# BTB_CONNECTOR.net
KiCad netlist of a schematic drawn in Altium Designer
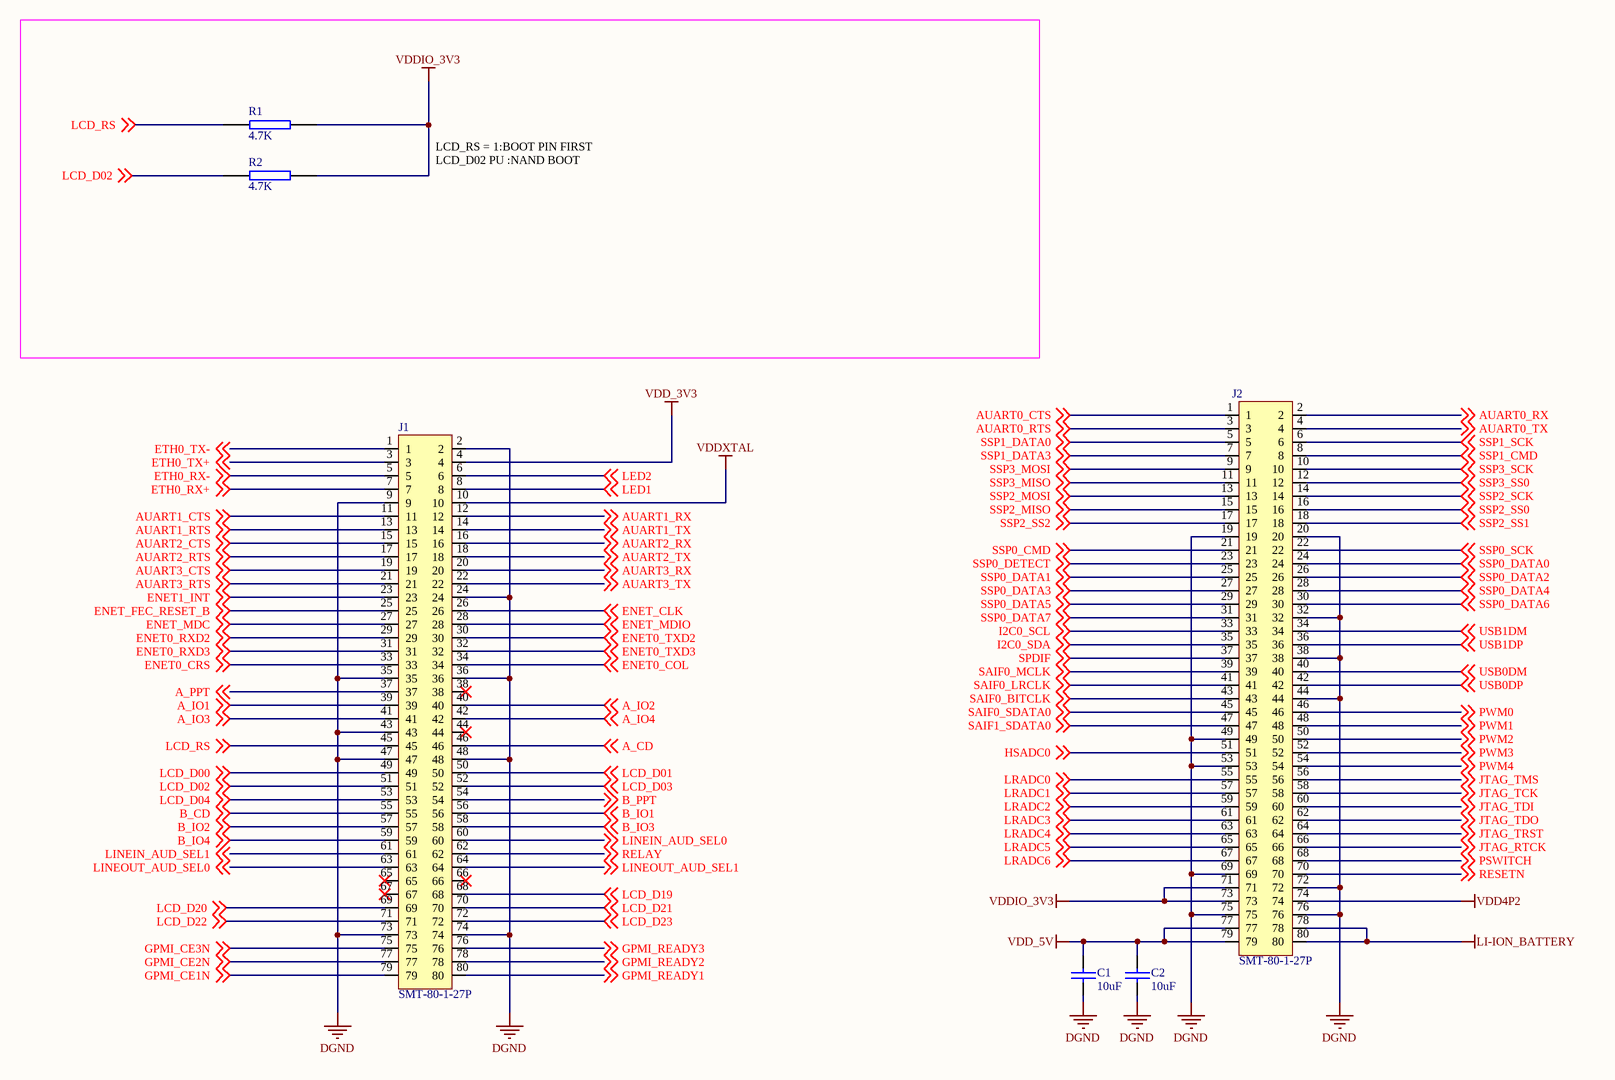
[diagram p0: BTB CONNECTOR.SchDoc]

(export (version "E")
  (design (tool "Eeschema 10.0.6"))
  (components
    (comp (ref "C1")
      (value "10uF")
      (footprint "C0805")
      (description "Capacitor")
      (libsource (lib "AirGateway") (part "CAP"))
    )
    (comp (ref "C2")
      (value "10uF")
      (footprint "C0805")
      (description "Capacitor")
      (libsource (lib "AirGateway") (part "CAP"))
    )
    (comp (ref "J1")
      (value "SMT-80-1-27P")
      (footprint "DB40X2-1.27")
      (libsource (lib "Schlib1") (part "SMT-80-1-27P"))
    )
    (comp (ref "J2")
      (value "SMT-80-1-27P")
      (footprint "DB40X2-1.27")
      (libsource (lib "Schlib1") (part "SMT-80-1-27P"))
    )
    (comp (ref "R1") (value "4.7K") (footprint "0603") (libsource (lib "AirGateway") (part "RES2")))
    (comp (ref "R2") (value "4.7K") (footprint "0603") (libsource (lib "AirGateway") (part "RES2")))
  )
  (nets
    (net (code "1") (name "AUART0_CTS") (class "Default")
      (node (ref "J2") (pin "1") (pinfunction "1_1") (pintype "passive"))
    )
    (net (code "2") (name "AUART0_RTS") (class "Default")
      (node (ref "J2") (pin "3") (pinfunction "3_3") (pintype "passive"))
    )
    (net (code "3") (name "AUART0_RX") (class "Default")
      (node (ref "J2") (pin "2") (pinfunction "2_2") (pintype "passive"))
    )
    (net (code "4") (name "AUART0_TX") (class "Default")
      (node (ref "J2") (pin "4") (pinfunction "4_4") (pintype "passive"))
    )
    (net (code "5") (name "AUART1_CTS") (class "Default")
      (node (ref "J1") (pin "11") (pinfunction "11_11") (pintype "passive"))
    )
    (net (code "6") (name "AUART1_RTS") (class "Default")
      (node (ref "J1") (pin "13") (pinfunction "13_13") (pintype "passive"))
    )
    (net (code "7") (name "AUART1_RX") (class "Default")
      (node (ref "J1") (pin "12") (pinfunction "12_12") (pintype "passive"))
    )
    (net (code "8") (name "AUART1_TX") (class "Default")
      (node (ref "J1") (pin "14") (pinfunction "14_14") (pintype "passive"))
    )
    (net (code "9") (name "AUART2_CTS") (class "Default")
      (node (ref "J1") (pin "15") (pinfunction "15_15") (pintype "passive"))
    )
    (net (code "10") (name "AUART2_RTS") (class "Default")
      (node (ref "J1") (pin "17") (pinfunction "17_17") (pintype "passive"))
    )
    (net (code "11") (name "AUART2_RX") (class "Default")
      (node (ref "J1") (pin "16") (pinfunction "16_16") (pintype "passive"))
    )
    (net (code "12") (name "AUART2_TX") (class "Default")
      (node (ref "J1") (pin "18") (pinfunction "18_18") (pintype "passive"))
    )
    (net (code "13") (name "AUART3_CTS") (class "Default")
      (node (ref "J1") (pin "19") (pinfunction "19_19") (pintype "passive"))
    )
    (net (code "14") (name "AUART3_RTS") (class "Default")
      (node (ref "J1") (pin "21") (pinfunction "21_21") (pintype "passive"))
    )
    (net (code "15") (name "AUART3_RX") (class "Default")
      (node (ref "J1") (pin "20") (pinfunction "20_20") (pintype "passive"))
    )
    (net (code "16") (name "AUART3_TX") (class "Default")
      (node (ref "J1") (pin "22") (pinfunction "22_22") (pintype "passive"))
    )
    (net (code "17") (name "A_CD") (class "Default")
      (node (ref "J1") (pin "46") (pinfunction "46_46") (pintype "passive"))
    )
    (net (code "18") (name "A_IO1") (class "Default")
      (node (ref "J1") (pin "39") (pinfunction "39_39") (pintype "passive"))
    )
    (net (code "19") (name "A_IO2") (class "Default")
      (node (ref "J1") (pin "40") (pinfunction "40_40") (pintype "passive"))
    )
    (net (code "20") (name "A_IO3") (class "Default")
      (node (ref "J1") (pin "41") (pinfunction "41_41") (pintype "passive"))
    )
    (net (code "21") (name "A_IO4") (class "Default")
      (node (ref "J1") (pin "42") (pinfunction "42_42") (pintype "passive"))
    )
    (net (code "22") (name "A_PPT") (class "Default")
      (node (ref "J1") (pin "37") (pinfunction "37_37") (pintype "passive"))
    )
    (net (code "23") (name "B_CD") (class "Default")
      (node (ref "J1") (pin "55") (pinfunction "55_55") (pintype "passive"))
    )
    (net (code "24") (name "B_IO1") (class "Default")
      (node (ref "J1") (pin "56") (pinfunction "56_56") (pintype "passive"))
    )
    (net (code "25") (name "B_IO2") (class "Default")
      (node (ref "J1") (pin "57") (pinfunction "57_57") (pintype "passive"))
    )
    (net (code "26") (name "B_IO3") (class "Default")
      (node (ref "J1") (pin "58") (pinfunction "58_58") (pintype "passive"))
    )
    (net (code "27") (name "B_IO4") (class "Default")
      (node (ref "J1") (pin "59") (pinfunction "59_59") (pintype "passive"))
    )
    (net (code "28") (name "B_PPT") (class "Default")
      (node (ref "J1") (pin "54") (pinfunction "54_54") (pintype "passive"))
    )
    (net (code "29") (name "DGND") (class "Default")
      (node (ref "C1") (pin "2") (pinfunction "2_2") (pintype "passive"))
      (node (ref "C2") (pin "2") (pinfunction "2_2") (pintype "passive"))
      (node (ref "J1") (pin "2") (pinfunction "2_2") (pintype "passive"))
      (node (ref "J1") (pin "24") (pinfunction "24_24") (pintype "passive"))
      (node (ref "J1") (pin "35") (pinfunction "35_35") (pintype "passive"))
      (node (ref "J1") (pin "36") (pinfunction "36_36") (pintype "passive"))
      (node (ref "J1") (pin "43") (pinfunction "43_43") (pintype "passive"))
      (node (ref "J1") (pin "47") (pinfunction "47_47") (pintype "passive"))
      (node (ref "J1") (pin "48") (pinfunction "48_48") (pintype "passive"))
      (node (ref "J1") (pin "73") (pinfunction "73_73") (pintype "passive"))
      (node (ref "J1") (pin "74") (pinfunction "74_74") (pintype "passive"))
      (node (ref "J1") (pin "9") (pinfunction "9_9") (pintype "passive"))
      (node (ref "J2") (pin "19") (pinfunction "19_19") (pintype "passive"))
      (node (ref "J2") (pin "20") (pinfunction "20_20") (pintype "passive"))
      (node (ref "J2") (pin "32") (pinfunction "32_32") (pintype "passive"))
      (node (ref "J2") (pin "38") (pinfunction "38_38") (pintype "passive"))
      (node (ref "J2") (pin "44") (pinfunction "44_44") (pintype "passive"))
      (node (ref "J2") (pin "49") (pinfunction "49_49") (pintype "passive"))
      (node (ref "J2") (pin "53") (pinfunction "53_53") (pintype "passive"))
      (node (ref "J2") (pin "69") (pinfunction "69_69") (pintype "passive"))
      (node (ref "J2") (pin "72") (pinfunction "72_72") (pintype "passive"))
      (node (ref "J2") (pin "75") (pinfunction "75_75") (pintype "passive"))
      (node (ref "J2") (pin "76") (pinfunction "76_76") (pintype "passive"))
    )
    (net (code "30") (name "ENET0_COL") (class "Default")
      (node (ref "J1") (pin "34") (pinfunction "34_34") (pintype "passive"))
    )
    (net (code "31") (name "ENET0_CRS") (class "Default")
      (node (ref "J1") (pin "33") (pinfunction "33_33") (pintype "passive"))
    )
    (net (code "32") (name "ENET0_RXD2") (class "Default")
      (node (ref "J1") (pin "29") (pinfunction "29_29") (pintype "passive"))
    )
    (net (code "33") (name "ENET0_RXD3") (class "Default")
      (node (ref "J1") (pin "31") (pinfunction "31_31") (pintype "passive"))
    )
    (net (code "34") (name "ENET0_TXD2") (class "Default")
      (node (ref "J1") (pin "30") (pinfunction "30_30") (pintype "passive"))
    )
    (net (code "35") (name "ENET0_TXD3") (class "Default")
      (node (ref "J1") (pin "32") (pinfunction "32_32") (pintype "passive"))
    )
    (net (code "36") (name "ENET1_INT") (class "Default")
      (node (ref "J1") (pin "23") (pinfunction "23_23") (pintype "passive"))
    )
    (net (code "37") (name "ENET_CLK") (class "Default")
      (node (ref "J1") (pin "26") (pinfunction "26_26") (pintype "passive"))
    )
    (net (code "38") (name "ENET_FEC_RESET_B") (class "Default")
      (node (ref "J1") (pin "25") (pinfunction "25_25") (pintype "passive"))
    )
    (net (code "39") (name "ENET_MDC") (class "Default")
      (node (ref "J1") (pin "27") (pinfunction "27_27") (pintype "passive"))
    )
    (net (code "40") (name "ENET_MDIO") (class "Default")
      (node (ref "J1") (pin "28") (pinfunction "28_28") (pintype "passive"))
    )
    (net (code "41") (name "ETH0_RX+") (class "Default")
      (node (ref "J1") (pin "7") (pinfunction "7_7") (pintype "passive"))
    )
    (net (code "42") (name "ETH0_RX-") (class "Default")
      (node (ref "J1") (pin "5") (pinfunction "5_5") (pintype "passive"))
    )
    (net (code "43") (name "ETH0_TX+") (class "Default")
      (node (ref "J1") (pin "3") (pinfunction "3_3") (pintype "passive"))
    )
    (net (code "44") (name "ETH0_TX-") (class "Default")
      (node (ref "J1") (pin "1") (pinfunction "1_1") (pintype "passive"))
    )
    (net (code "45") (name "GPMI_CE1N") (class "Default")
      (node (ref "J1") (pin "79") (pinfunction "79_79") (pintype "passive"))
    )
    (net (code "46") (name "GPMI_CE2N") (class "Default")
      (node (ref "J1") (pin "77") (pinfunction "77_77") (pintype "passive"))
    )
    (net (code "47") (name "GPMI_CE3N") (class "Default")
      (node (ref "J1") (pin "75") (pinfunction "75_75") (pintype "passive"))
    )
    (net (code "48") (name "GPMI_READY1") (class "Default")
      (node (ref "J1") (pin "80") (pinfunction "80_80") (pintype "passive"))
    )
    (net (code "49") (name "GPMI_READY2") (class "Default")
      (node (ref "J1") (pin "78") (pinfunction "78_78") (pintype "passive"))
    )
    (net (code "50") (name "GPMI_READY3") (class "Default")
      (node (ref "J1") (pin "76") (pinfunction "76_76") (pintype "passive"))
    )
    (net (code "51") (name "HSADC0") (class "Default")
      (node (ref "J2") (pin "51") (pinfunction "51_51") (pintype "passive"))
    )
    (net (code "52") (name "I2C0_SCL") (class "Default")
      (node (ref "J2") (pin "33") (pinfunction "33_33") (pintype "passive"))
    )
    (net (code "53") (name "I2C0_SDA") (class "Default")
      (node (ref "J2") (pin "35") (pinfunction "35_35") (pintype "passive"))
    )
    (net (code "54") (name "JTAG_RTCK") (class "Default")
      (node (ref "J2") (pin "66") (pinfunction "66_66") (pintype "passive"))
    )
    (net (code "55") (name "JTAG_TCK") (class "Default")
      (node (ref "J2") (pin "58") (pinfunction "58_58") (pintype "passive"))
    )
    (net (code "56") (name "JTAG_TDI") (class "Default")
      (node (ref "J2") (pin "60") (pinfunction "60_60") (pintype "passive"))
    )
    (net (code "57") (name "JTAG_TDO") (class "Default")
      (node (ref "J2") (pin "62") (pinfunction "62_62") (pintype "passive"))
    )
    (net (code "58") (name "JTAG_TMS") (class "Default")
      (node (ref "J2") (pin "56") (pinfunction "56_56") (pintype "passive"))
    )
    (net (code "59") (name "JTAG_TRST") (class "Default")
      (node (ref "J2") (pin "64") (pinfunction "64_64") (pintype "passive"))
    )
    (net (code "60") (name "LCD_D00") (class "Default")
      (node (ref "J1") (pin "49") (pinfunction "49_49") (pintype "passive"))
    )
    (net (code "61") (name "LCD_D01") (class "Default")
      (node (ref "J1") (pin "50") (pinfunction "50_50") (pintype "passive"))
    )
    (net (code "62") (name "LCD_D02") (class "Default")
      (node (ref "J1") (pin "51") (pinfunction "51_51") (pintype "passive"))
      (node (ref "R2") (pin "2") (pinfunction "2_2") (pintype "passive"))
    )
    (net (code "63") (name "LCD_D03") (class "Default")
      (node (ref "J1") (pin "52") (pinfunction "52_52") (pintype "passive"))
    )
    (net (code "64") (name "LCD_D04") (class "Default")
      (node (ref "J1") (pin "53") (pinfunction "53_53") (pintype "passive"))
    )
    (net (code "65") (name "LCD_D19") (class "Default")
      (node (ref "J1") (pin "68") (pinfunction "68_68") (pintype "passive"))
    )
    (net (code "66") (name "LCD_D20") (class "Default")
      (node (ref "J1") (pin "69") (pinfunction "69_69") (pintype "passive"))
    )
    (net (code "67") (name "LCD_D21") (class "Default")
      (node (ref "J1") (pin "70") (pinfunction "70_70") (pintype "passive"))
    )
    (net (code "68") (name "LCD_D22") (class "Default")
      (node (ref "J1") (pin "71") (pinfunction "71_71") (pintype "passive"))
    )
    (net (code "69") (name "LCD_D23") (class "Default")
      (node (ref "J1") (pin "72") (pinfunction "72_72") (pintype "passive"))
    )
    (net (code "70") (name "LCD_RS") (class "Default")
      (node (ref "J1") (pin "45") (pinfunction "45_45") (pintype "passive"))
      (node (ref "R1") (pin "2") (pinfunction "2_2") (pintype "passive"))
    )
    (net (code "71") (name "LED1") (class "Default")
      (node (ref "J1") (pin "8") (pinfunction "8_8") (pintype "passive"))
    )
    (net (code "72") (name "LED2") (class "Default")
      (node (ref "J1") (pin "6") (pinfunction "6_6") (pintype "passive"))
    )
    (net (code "73") (name "LI-ION_BATTERY") (class "Default")
      (node (ref "J2") (pin "78") (pinfunction "78_78") (pintype "passive"))
      (node (ref "J2") (pin "80") (pinfunction "80_80") (pintype "passive"))
    )
    (net (code "74") (name "LINEIN_AUD_SEL0") (class "Default")
      (node (ref "J1") (pin "60") (pinfunction "60_60") (pintype "passive"))
    )
    (net (code "75") (name "LINEIN_AUD_SEL1") (class "Default")
      (node (ref "J1") (pin "61") (pinfunction "61_61") (pintype "passive"))
    )
    (net (code "76") (name "LINEOUT_AUD_SEL0") (class "Default")
      (node (ref "J1") (pin "63") (pinfunction "63_63") (pintype "passive"))
    )
    (net (code "77") (name "LINEOUT_AUD_SEL1") (class "Default")
      (node (ref "J1") (pin "64") (pinfunction "64_64") (pintype "passive"))
    )
    (net (code "78") (name "LRADC0") (class "Default")
      (node (ref "J2") (pin "55") (pinfunction "55_55") (pintype "passive"))
    )
    (net (code "79") (name "LRADC1") (class "Default")
      (node (ref "J2") (pin "57") (pinfunction "57_57") (pintype "passive"))
    )
    (net (code "80") (name "LRADC2") (class "Default")
      (node (ref "J2") (pin "59") (pinfunction "59_59") (pintype "passive"))
    )
    (net (code "81") (name "LRADC3") (class "Default")
      (node (ref "J2") (pin "61") (pinfunction "61_61") (pintype "passive"))
    )
    (net (code "82") (name "LRADC4") (class "Default")
      (node (ref "J2") (pin "63") (pinfunction "63_63") (pintype "passive"))
    )
    (net (code "83") (name "LRADC5") (class "Default")
      (node (ref "J2") (pin "65") (pinfunction "65_65") (pintype "passive"))
    )
    (net (code "84") (name "LRADC6") (class "Default")
      (node (ref "J2") (pin "67") (pinfunction "67_67") (pintype "passive"))
    )
    (net (code "85") (name "PSWITCH") (class "Default")
      (node (ref "J2") (pin "68") (pinfunction "68_68") (pintype "passive"))
    )
    (net (code "86") (name "PWM0") (class "Default")
      (node (ref "J2") (pin "46") (pinfunction "46_46") (pintype "passive"))
    )
    (net (code "87") (name "PWM1") (class "Default")
      (node (ref "J2") (pin "48") (pinfunction "48_48") (pintype "passive"))
    )
    (net (code "88") (name "PWM2") (class "Default")
      (node (ref "J2") (pin "50") (pinfunction "50_50") (pintype "passive"))
    )
    (net (code "89") (name "PWM3") (class "Default")
      (node (ref "J2") (pin "52") (pinfunction "52_52") (pintype "passive"))
    )
    (net (code "90") (name "PWM4") (class "Default")
      (node (ref "J2") (pin "54") (pinfunction "54_54") (pintype "passive"))
    )
    (net (code "91") (name "RELAY") (class "Default")
      (node (ref "J1") (pin "62") (pinfunction "62_62") (pintype "passive"))
    )
    (net (code "92") (name "RESETN") (class "Default")
      (node (ref "J2") (pin "70") (pinfunction "70_70") (pintype "passive"))
    )
    (net (code "93") (name "SAIF0_BITCLK") (class "Default")
      (node (ref "J2") (pin "43") (pinfunction "43_43") (pintype "passive"))
    )
    (net (code "94") (name "SAIF0_LRCLK") (class "Default")
      (node (ref "J2") (pin "41") (pinfunction "41_41") (pintype "passive"))
    )
    (net (code "95") (name "SAIF0_MCLK") (class "Default")
      (node (ref "J2") (pin "39") (pinfunction "39_39") (pintype "passive"))
    )
    (net (code "96") (name "SAIF0_SDATA0") (class "Default")
      (node (ref "J2") (pin "45") (pinfunction "45_45") (pintype "passive"))
    )
    (net (code "97") (name "SAIF1_SDATA0") (class "Default")
      (node (ref "J2") (pin "47") (pinfunction "47_47") (pintype "passive"))
    )
    (net (code "98") (name "SPDIF") (class "Default")
      (node (ref "J2") (pin "37") (pinfunction "37_37") (pintype "passive"))
    )
    (net (code "99") (name "SSP0_CMD") (class "Default")
      (node (ref "J2") (pin "21") (pinfunction "21_21") (pintype "passive"))
    )
    (net (code "100") (name "SSP0_DATA0") (class "Default")
      (node (ref "J2") (pin "24") (pinfunction "24_24") (pintype "passive"))
    )
    (net (code "101") (name "SSP0_DATA1") (class "Default")
      (node (ref "J2") (pin "25") (pinfunction "25_25") (pintype "passive"))
    )
    (net (code "102") (name "SSP0_DATA2") (class "Default")
      (node (ref "J2") (pin "26") (pinfunction "26_26") (pintype "passive"))
    )
    (net (code "103") (name "SSP0_DATA3") (class "Default")
      (node (ref "J2") (pin "27") (pinfunction "27_27") (pintype "passive"))
    )
    (net (code "104") (name "SSP0_DATA4") (class "Default")
      (node (ref "J2") (pin "28") (pinfunction "28_28") (pintype "passive"))
    )
    (net (code "105") (name "SSP0_DATA5") (class "Default")
      (node (ref "J2") (pin "29") (pinfunction "29_29") (pintype "passive"))
    )
    (net (code "106") (name "SSP0_DATA6") (class "Default")
      (node (ref "J2") (pin "30") (pinfunction "30_30") (pintype "passive"))
    )
    (net (code "107") (name "SSP0_DATA7") (class "Default")
      (node (ref "J2") (pin "31") (pinfunction "31_31") (pintype "passive"))
    )
    (net (code "108") (name "SSP0_DETECT") (class "Default")
      (node (ref "J2") (pin "23") (pinfunction "23_23") (pintype "passive"))
    )
    (net (code "109") (name "SSP0_SCK") (class "Default")
      (node (ref "J2") (pin "22") (pinfunction "22_22") (pintype "passive"))
    )
    (net (code "110") (name "SSP1_CMD") (class "Default")
      (node (ref "J2") (pin "8") (pinfunction "8_8") (pintype "passive"))
    )
    (net (code "111") (name "SSP1_DATA0") (class "Default")
      (node (ref "J2") (pin "5") (pinfunction "5_5") (pintype "passive"))
    )
    (net (code "112") (name "SSP1_DATA3") (class "Default")
      (node (ref "J2") (pin "7") (pinfunction "7_7") (pintype "passive"))
    )
    (net (code "113") (name "SSP1_SCK") (class "Default")
      (node (ref "J2") (pin "6") (pinfunction "6_6") (pintype "passive"))
    )
    (net (code "114") (name "SSP2_MISO") (class "Default")
      (node (ref "J2") (pin "15") (pinfunction "15_15") (pintype "passive"))
    )
    (net (code "115") (name "SSP2_MOSI") (class "Default")
      (node (ref "J2") (pin "13") (pinfunction "13_13") (pintype "passive"))
    )
    (net (code "116") (name "SSP2_SCK") (class "Default")
      (node (ref "J2") (pin "14") (pinfunction "14_14") (pintype "passive"))
    )
    (net (code "117") (name "SSP2_SS0") (class "Default")
      (node (ref "J2") (pin "16") (pinfunction "16_16") (pintype "passive"))
    )
    (net (code "118") (name "SSP2_SS1") (class "Default")
      (node (ref "J2") (pin "18") (pinfunction "18_18") (pintype "passive"))
    )
    (net (code "119") (name "SSP2_SS2") (class "Default")
      (node (ref "J2") (pin "17") (pinfunction "17_17") (pintype "passive"))
    )
    (net (code "120") (name "SSP3_MISO") (class "Default")
      (node (ref "J2") (pin "11") (pinfunction "11_11") (pintype "passive"))
    )
    (net (code "121") (name "SSP3_MOSI") (class "Default")
      (node (ref "J2") (pin "9") (pinfunction "9_9") (pintype "passive"))
    )
    (net (code "122") (name "SSP3_SCK") (class "Default")
      (node (ref "J2") (pin "10") (pinfunction "10_10") (pintype "passive"))
    )
    (net (code "123") (name "SSP3_SS0") (class "Default")
      (node (ref "J2") (pin "12") (pinfunction "12_12") (pintype "passive"))
    )
    (net (code "124") (name "USB0DM") (class "Default")
      (node (ref "J2") (pin "40") (pinfunction "40_40") (pintype "passive"))
    )
    (net (code "125") (name "USB0DP") (class "Default")
      (node (ref "J2") (pin "42") (pinfunction "42_42") (pintype "passive"))
    )
    (net (code "126") (name "USB1DM") (class "Default")
      (node (ref "J2") (pin "34") (pinfunction "34_34") (pintype "passive"))
    )
    (net (code "127") (name "USB1DP") (class "Default")
      (node (ref "J2") (pin "36") (pinfunction "36_36") (pintype "passive"))
    )
    (net (code "128") (name "VDD4P2") (class "Default")
      (node (ref "J2") (pin "74") (pinfunction "74_74") (pintype "passive"))
    )
    (net (code "129") (name "VDDIO_3V3") (class "Default")
      (node (ref "J2") (pin "71") (pinfunction "71_71") (pintype "passive"))
      (node (ref "J2") (pin "73") (pinfunction "73_73") (pintype "passive"))
      (node (ref "R1") (pin "1") (pinfunction "1_1") (pintype "passive"))
      (node (ref "R2") (pin "1") (pinfunction "1_1") (pintype "passive"))
    )
    (net (code "130") (name "VDDXTAL") (class "Default")
      (node (ref "J1") (pin "10") (pinfunction "10_10") (pintype "passive"))
    )
    (net (code "131") (name "VDD_3V3") (class "Default")
      (node (ref "J1") (pin "4") (pinfunction "4_4") (pintype "passive"))
    )
    (net (code "132") (name "VDD_5V") (class "Default")
      (node (ref "C1") (pin "1") (pinfunction "1_1") (pintype "passive"))
      (node (ref "C2") (pin "1") (pinfunction "1_1") (pintype "passive"))
      (node (ref "J2") (pin "77") (pinfunction "77_77") (pintype "passive"))
      (node (ref "J2") (pin "79") (pinfunction "79_79") (pintype "passive"))
    )
    (net (code "133") (name "unconnected-(J1-Pad38)") (class "Default")
      (node (ref "J1") (pin "38") (pinfunction "38_38") (pintype "passive+no_connect"))
    )
    (net (code "134") (name "unconnected-(J1-Pad44)") (class "Default")
      (node (ref "J1") (pin "44") (pinfunction "44_44") (pintype "passive+no_connect"))
    )
    (net (code "135") (name "unconnected-(J1-Pad65)") (class "Default")
      (node (ref "J1") (pin "65") (pinfunction "65_65") (pintype "passive+no_connect"))
    )
    (net (code "136") (name "unconnected-(J1-Pad66)") (class "Default")
      (node (ref "J1") (pin "66") (pinfunction "66_66") (pintype "passive+no_connect"))
    )
    (net (code "137") (name "unconnected-(J1-Pad67)") (class "Default")
      (node (ref "J1") (pin "67") (pinfunction "67_67") (pintype "passive+no_connect"))
    )
  )
)
